# schema_pm.net
KiCad netlist of a schematic drawn in EAGLE
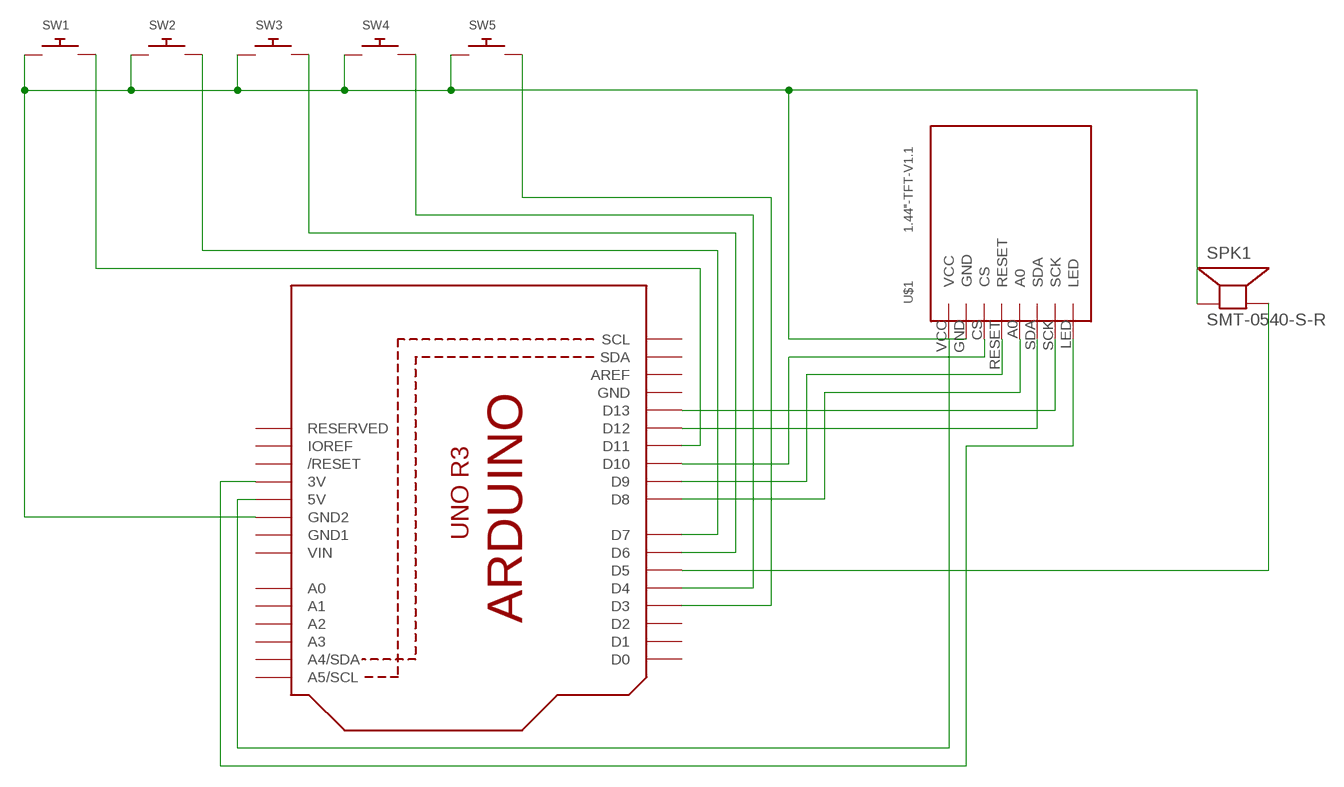
[diagram p0: schematic, sheet 1]

(export (version "E")
  (design (tool "Eeschema 10.0.6"))
  (components
    (comp (ref "SPK1")
      (value "SMT-0540-S-R")
      (footprint "eagle-import:SMT-0540-S-R")
      (libsource (lib "eagle-import") (part "SMT-0540-S-R"))
    )
    (comp (ref "SW1")
      (value "SWITCH_PUSHBUTTONC&K_KSS")
      (footprint "eagle-import:BTN_CK_KSS")
      (libsource (lib "eagle-import") (part "SWITCH_PUSHBUTTONC&K_KSS"))
    )
    (comp (ref "SW2")
      (value "SWITCH_PUSHBUTTONC&K_KSS")
      (footprint "eagle-import:BTN_CK_KSS")
      (libsource (lib "eagle-import") (part "SWITCH_PUSHBUTTONC&K_KSS"))
    )
    (comp (ref "SW3")
      (value "SWITCH_PUSHBUTTONC&K_KSS")
      (footprint "eagle-import:BTN_CK_KSS")
      (libsource (lib "eagle-import") (part "SWITCH_PUSHBUTTONC&K_KSS"))
    )
    (comp (ref "SW4")
      (value "SWITCH_PUSHBUTTONC&K_KSS")
      (footprint "eagle-import:BTN_CK_KSS")
      (libsource (lib "eagle-import") (part "SWITCH_PUSHBUTTONC&K_KSS"))
    )
    (comp (ref "SW5")
      (value "SWITCH_PUSHBUTTONC&K_KSS")
      (footprint "eagle-import:BTN_CK_KSS")
      (libsource (lib "eagle-import") (part "SWITCH_PUSHBUTTONC&K_KSS"))
    )
    (comp (ref "U$1")
      (value "1.44\"-TFT-V1.1")
      (footprint "eagle-import:1.44-TFT-V1.1")
      (libsource (lib "eagle-import") (part "1.44{dblquote}-TFT-V1.1"))
    )
    (comp (ref "U1")
      (value "ARDUINOR3-BPLACE")
      (footprint "eagle-import:ARDUINOR3-BPLACE")
      (libsource (lib "eagle-import") (part "ARDUINOR3-BPLACE"))
    )
  )
  (nets
    (net (code "1") (name "/GND") (class "Default")
      (node (ref "U1") (pin "GND") (pinfunction "GND_GND") (pintype "power_in"))
    )
    (net (code "2") (name "/GND1") (class "Default")
      (node (ref "U1") (pin "GND1") (pinfunction "GND1_GND1") (pintype "power_in"))
    )
    (net (code "3") (name "/VIN") (class "Default")
      (node (ref "U1") (pin "VIN") (pinfunction "VIN_VIN") (pintype "power_in"))
    )
    (net (code "4") (name "Net-(SPK1-+)") (class "Default")
      (node (ref "SPK1") (pin "-") (pinfunction "+_-") (pintype "passive"))
      (node (ref "SW1") (pin "P$1") (pinfunction "P$1_P$1") (pintype "passive"))
      (node (ref "SW2") (pin "P$1") (pinfunction "P$1_P$1") (pintype "passive"))
      (node (ref "SW3") (pin "P$1") (pinfunction "P$1_P$1") (pintype "passive"))
      (node (ref "SW4") (pin "P$1") (pinfunction "P$1_P$1") (pintype "passive"))
      (node (ref "SW5") (pin "P$1") (pinfunction "P$1_P$1") (pintype "passive"))
      (node (ref "U$1") (pin "GND") (pinfunction "GND_GND") (pintype "bidirectional"))
      (node (ref "U1") (pin "GND2") (pinfunction "GND2_GND2") (pintype "power_in"))
    )
    (net (code "5") (name "Net-(SPK1--)") (class "Default")
      (node (ref "SPK1") (pin "+") (pinfunction "-_+") (pintype "passive"))
      (node (ref "U1") (pin "D5") (pinfunction "D5_D5") (pintype "bidirectional"))
    )
    (net (code "6") (name "Net-(SW1-PadP$2)") (class "Default")
      (node (ref "SW1") (pin "P$2") (pinfunction "P$2_P$2") (pintype "passive"))
      (node (ref "U1") (pin "D11") (pinfunction "D11_D11") (pintype "bidirectional"))
    )
    (net (code "7") (name "Net-(SW2-PadP$2)") (class "Default")
      (node (ref "SW2") (pin "P$2") (pinfunction "P$2_P$2") (pintype "passive"))
      (node (ref "U1") (pin "D7") (pinfunction "D7_D7") (pintype "bidirectional"))
    )
    (net (code "8") (name "Net-(SW3-PadP$2)") (class "Default")
      (node (ref "SW3") (pin "P$2") (pinfunction "P$2_P$2") (pintype "passive"))
      (node (ref "U1") (pin "D6") (pinfunction "D6_D6") (pintype "bidirectional"))
    )
    (net (code "9") (name "Net-(SW4-PadP$2)") (class "Default")
      (node (ref "SW4") (pin "P$2") (pinfunction "P$2_P$2") (pintype "passive"))
      (node (ref "U1") (pin "D4") (pinfunction "D4_D4") (pintype "bidirectional"))
    )
    (net (code "10") (name "Net-(SW5-PadP$2)") (class "Default")
      (node (ref "SW5") (pin "P$2") (pinfunction "P$2_P$2") (pintype "passive"))
      (node (ref "U1") (pin "D3") (pinfunction "D3_D3") (pintype "bidirectional"))
    )
    (net (code "11") (name "Net-(U$1-PadA0)") (class "Default")
      (node (ref "U$1") (pin "A0") (pinfunction "A0_A0") (pintype "bidirectional"))
      (node (ref "U1") (pin "D8") (pinfunction "D8_D8") (pintype "bidirectional"))
    )
    (net (code "12") (name "Net-(U$1-PadCS)") (class "Default")
      (node (ref "U$1") (pin "CS") (pinfunction "CS_CS") (pintype "bidirectional"))
      (node (ref "U1") (pin "D10") (pinfunction "D10_D10") (pintype "bidirectional"))
    )
    (net (code "13") (name "Net-(U$1-PadLED)") (class "Default")
      (node (ref "U$1") (pin "LED") (pinfunction "LED_LED") (pintype "bidirectional"))
      (node (ref "U1") (pin "3V") (pinfunction "3V_3V") (pintype "power_in"))
    )
    (net (code "14") (name "Net-(U$1-PadRESET)") (class "Default")
      (node (ref "U$1") (pin "RESET") (pinfunction "RESET_RESET") (pintype "bidirectional"))
      (node (ref "U1") (pin "D9") (pinfunction "D9_D9") (pintype "bidirectional"))
    )
    (net (code "15") (name "Net-(U$1-PadSCK)") (class "Default")
      (node (ref "U$1") (pin "SCK") (pinfunction "SCK_SCK") (pintype "bidirectional"))
      (node (ref "U1") (pin "D13") (pinfunction "D13_D13") (pintype "bidirectional"))
    )
    (net (code "16") (name "Net-(U$1-PadSDA)") (class "Default")
      (node (ref "U$1") (pin "SDA") (pinfunction "SDA_SDA") (pintype "bidirectional"))
      (node (ref "U1") (pin "D12") (pinfunction "D12_D12") (pintype "bidirectional"))
    )
    (net (code "17") (name "Net-(U$1-PadVCC)") (class "Default")
      (node (ref "U$1") (pin "VCC") (pinfunction "VCC_VCC") (pintype "bidirectional"))
      (node (ref "U1") (pin "5V") (pinfunction "5V_5V") (pintype "power_in"))
    )
    (net (code "18") (name "unconnected-(U1-A4{slash}SDA-PadA4)") (class "Default")
      (node (ref "U1") (pin "A4") (pinfunction "A4/SDA_A4") (pintype "bidirectional"))
    )
    (net (code "19") (name "unconnected-(U1-A5{slash}SCL-PadA5)") (class "Default")
      (node (ref "U1") (pin "A5") (pinfunction "A5/SCL_A5") (pintype "bidirectional"))
    )
    (net (code "20") (name "unconnected-(U1-PadA0)") (class "Default")
      (node (ref "U1") (pin "A0") (pinfunction "A0_A0") (pintype "bidirectional"))
    )
    (net (code "21") (name "unconnected-(U1-PadA1)") (class "Default")
      (node (ref "U1") (pin "A1") (pinfunction "A1_A1") (pintype "bidirectional"))
    )
    (net (code "22") (name "unconnected-(U1-PadA2)") (class "Default")
      (node (ref "U1") (pin "A2") (pinfunction "A2_A2") (pintype "bidirectional"))
    )
    (net (code "23") (name "unconnected-(U1-PadA3)") (class "Default")
      (node (ref "U1") (pin "A3") (pinfunction "A3_A3") (pintype "bidirectional"))
    )
    (net (code "24") (name "unconnected-(U1-PadAREF)") (class "Default")
      (node (ref "U1") (pin "AREF") (pinfunction "AREF_AREF") (pintype "bidirectional"))
    )
    (net (code "25") (name "unconnected-(U1-PadD0)") (class "Default")
      (node (ref "U1") (pin "D0") (pinfunction "D0_D0") (pintype "bidirectional"))
    )
    (net (code "26") (name "unconnected-(U1-PadD1)") (class "Default")
      (node (ref "U1") (pin "D1") (pinfunction "D1_D1") (pintype "bidirectional"))
    )
    (net (code "27") (name "unconnected-(U1-PadD2)") (class "Default")
      (node (ref "U1") (pin "D2") (pinfunction "D2_D2") (pintype "bidirectional"))
    )
    (net (code "28") (name "unconnected-(U1-PadIOREF)") (class "Default")
      (node (ref "U1") (pin "IOREF") (pinfunction "IOREF_IOREF") (pintype "output"))
    )
    (net (code "29") (name "unconnected-(U1-PadRESERVED)") (class "Default")
      (node (ref "U1") (pin "RESERVED") (pinfunction "RESERVED_RESERVED") (pintype "no_connect"))
    )
    (net (code "30") (name "unconnected-(U1-PadSCL)") (class "Default")
      (node (ref "U1") (pin "SCL") (pinfunction "SCL_SCL") (pintype "bidirectional"))
    )
    (net (code "31") (name "unconnected-(U1-PadSDA)") (class "Default")
      (node (ref "U1") (pin "SDA") (pinfunction "SDA_SDA") (pintype "bidirectional"))
    )
    (net (code "32") (name "unconnected-(U1-{slash}RESET-PadRESET)") (class "Default")
      (node (ref "U1") (pin "RESET") (pinfunction "/RESET_RESET") (pintype "bidirectional"))
    )
  )
)
